# Supply_core.net
KiCad netlist of a schematic drawn in Altium Designer
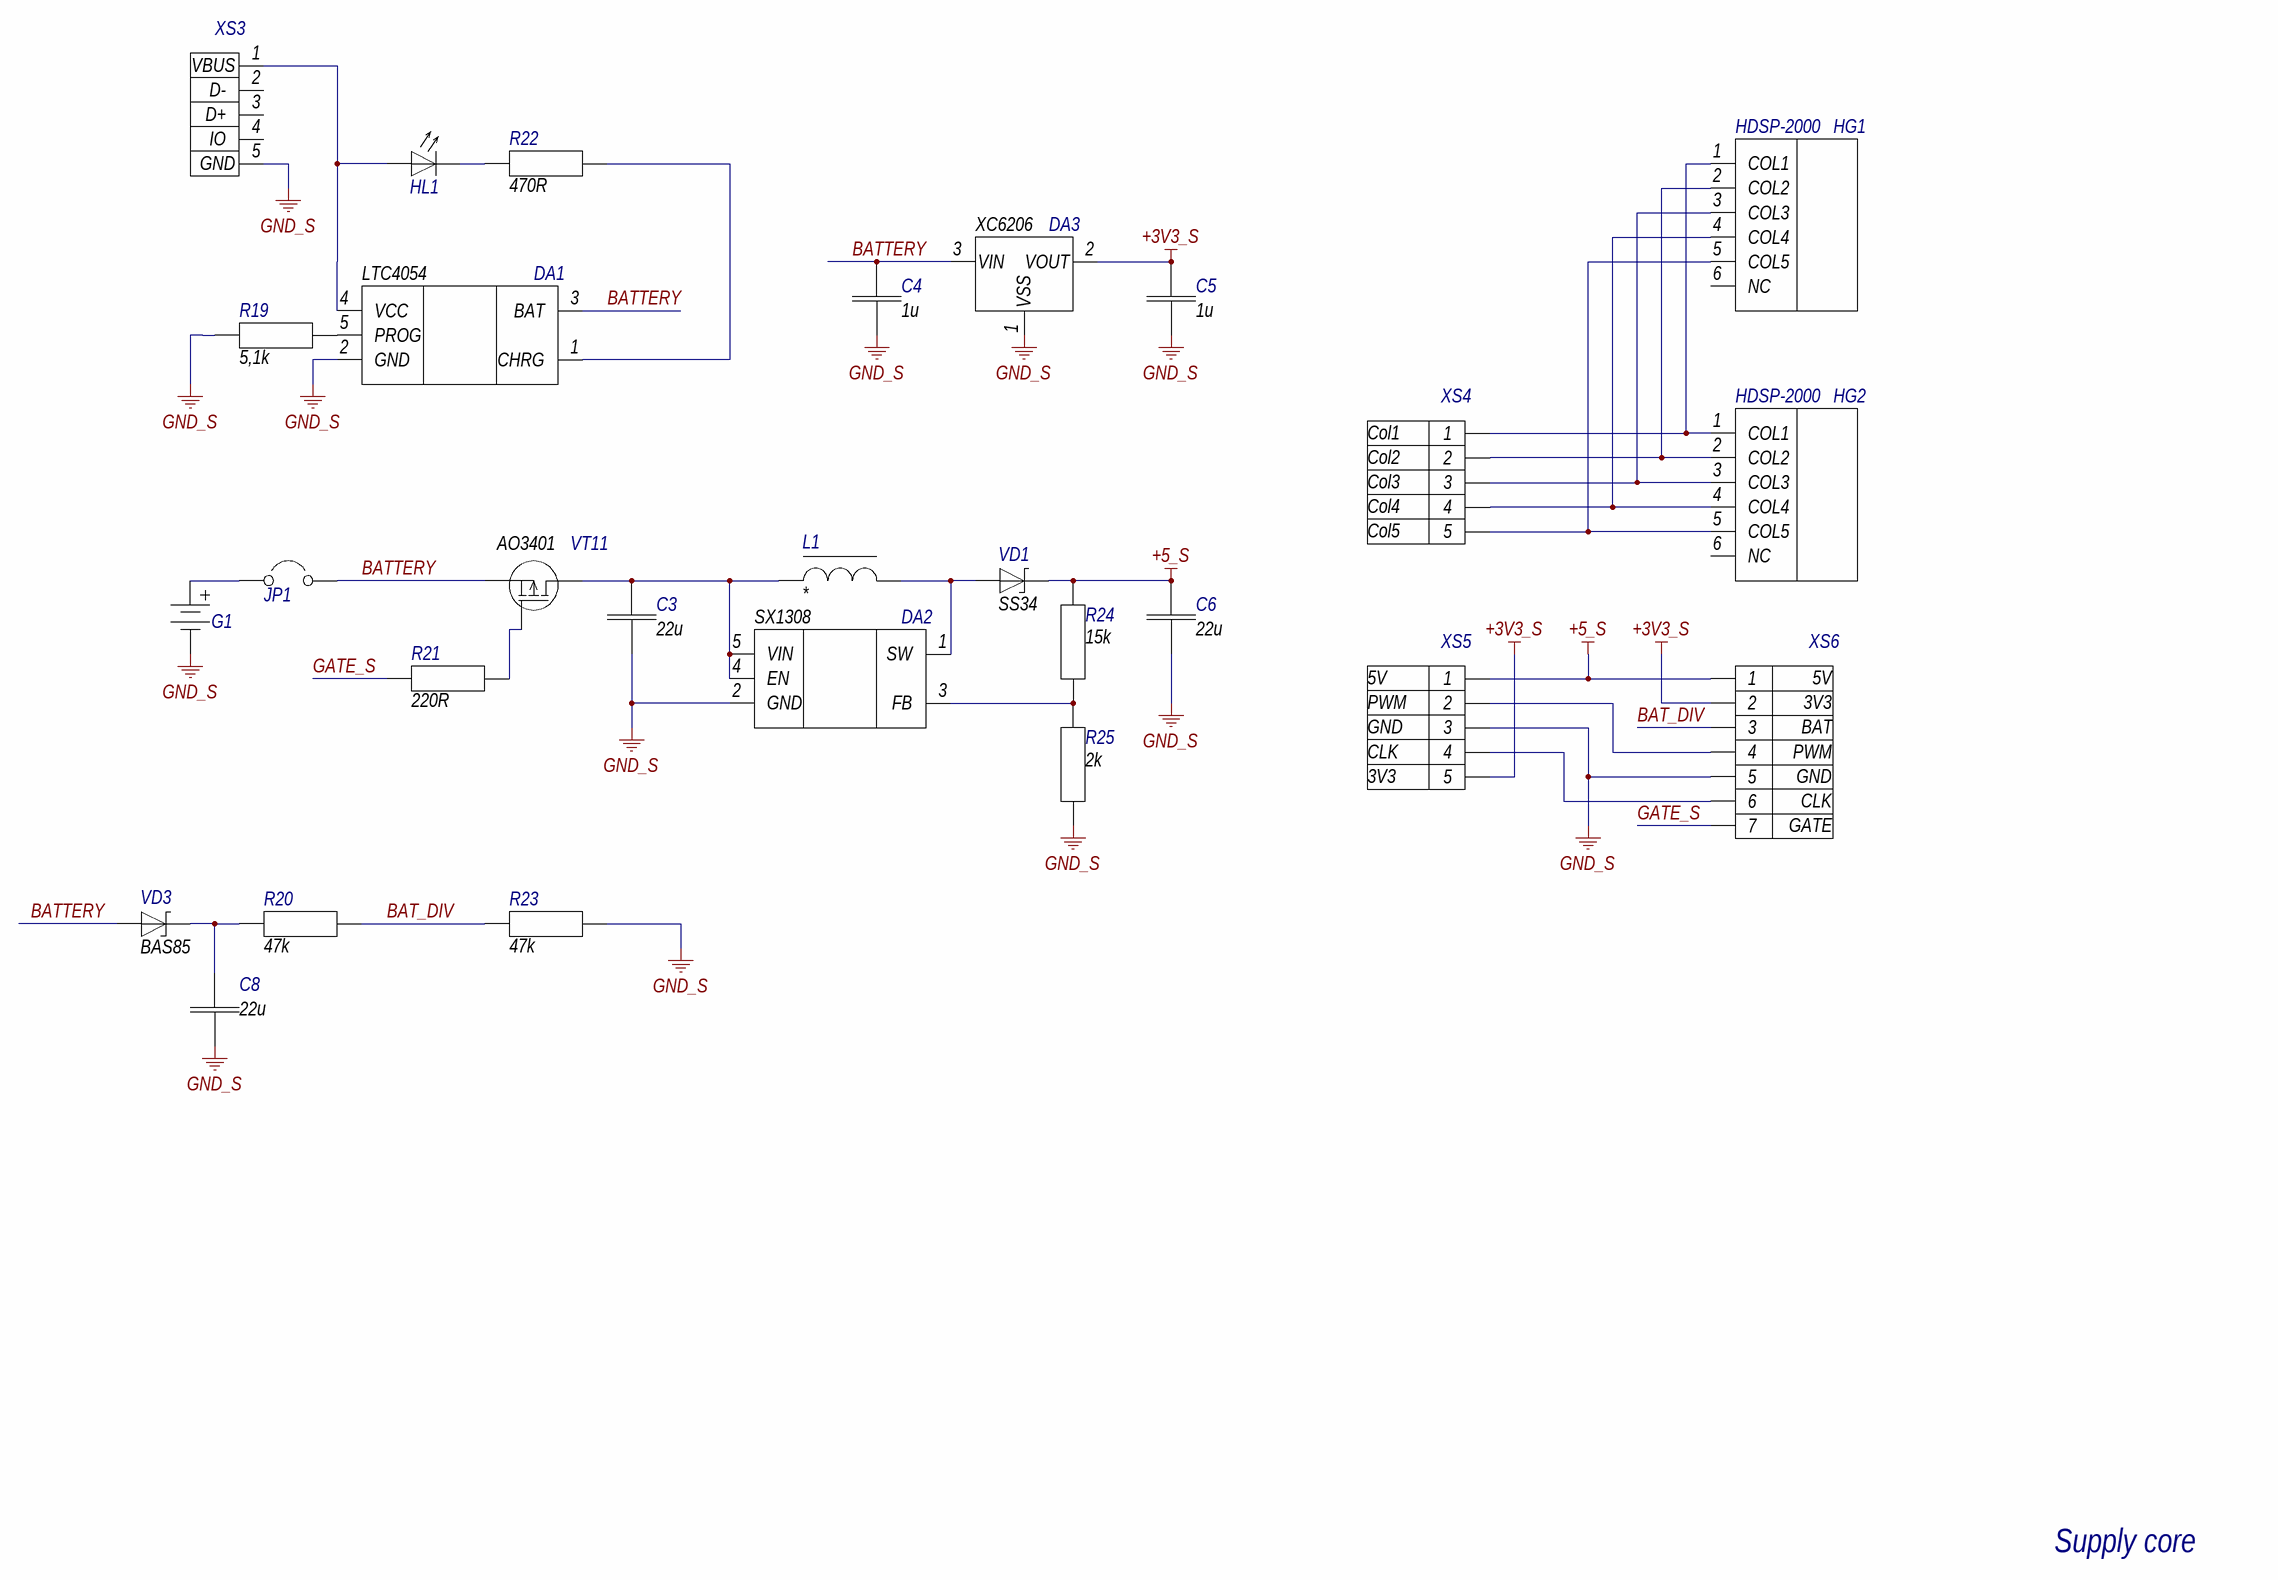
[diagram p0: Supply_core.SchDoc]

(export (version "E")
  (design (tool "Eeschema 10.0.6"))
  (components
    (comp (ref "C3")
      (value "22u")
      (footprint "CHIP-0805")
      (fields (field (name "Comment") "C0805"))
      (libsource (lib "Schlib1") (part "C0805"))
    )
    (comp (ref "C4")
      (value "1u")
      (footprint "CHIP-0603")
      (fields (field (name "Comment") "C0805"))
      (libsource (lib "Schlib1") (part "C0805"))
    )
    (comp (ref "C5")
      (value "1u")
      (footprint "CHIP-0603")
      (fields (field (name "Comment") "C0805"))
      (libsource (lib "Schlib1") (part "C0805"))
    )
    (comp (ref "C6")
      (value "22u")
      (footprint "CHIP-0805")
      (fields (field (name "Comment") "C0805"))
      (libsource (lib "Schlib1") (part "C0805"))
    )
    (comp (ref "C8")
      (value "22u")
      (footprint "CHIP-0805")
      (fields (field (name "Comment") "C0805"))
      (libsource (lib "Schlib1") (part "C0805"))
    )
    (comp (ref "DA1")
      (value "LTC4054")
      (footprint "SOT23-5")
      (fields (field (name "NAME") "LTC4054"))
      (libsource (lib "Schlib1") (part "LTC4054"))
    )
    (comp (ref "DA2")
      (value "SX1308")
      (footprint "SOT23-6")
      (fields (field (name "NAME") "SX1308"))
      (libsource (lib "Schlib1") (part "SX1308"))
    )
    (comp (ref "DA3")
      (value "XC6206")
      (footprint "SOT23-3")
      (fields (field (name "NAME") "XC6206"))
      (libsource (lib "Schlib1") (part "XC6206"))
    )
    (comp (ref "G1") (value "Battery") (footprint "BATTERY") (libsource (lib "Schlib1") (part "Battery")))
    (comp (ref "HG1")
      (value "HDSP-2000_Colums")
      (footprint "HDSP-2000_COL")
      (fields (field (name "MANUFACTURER") "HP") (field (name "NAME") "HDSP-2000"))
      (libsource (lib "Schlib1") (part "HDSP-2000_Colums"))
    )
    (comp (ref "HG2")
      (value "HDSP-2000_Colums")
      (footprint "HDSP-2000_COL")
      (fields (field (name "MANUFACTURER") "HP") (field (name "NAME") "HDSP-2000"))
      (libsource (lib "Schlib1") (part "HDSP-2000_Colums"))
    )
    (comp (ref "HL1") (value "LED") (footprint "LED_1") (libsource (lib "Schlib1") (part "LED")))
    (comp (ref "JP1") (value "Jamper") (footprint "JAMPER") (libsource (lib "Schlib1") (part "Jamper")))
    (comp (ref "L1")
      (value "L")
      (footprint "L_SMD")
      (fields (field (name "ALTIUM_VALUE") "*"))
      (libsource (lib "Schlib1") (part "L"))
    )
    (comp (ref "R19")
      (value "5,1k")
      (footprint "CHIP-0402")
      (fields (field (name "Comment") "R0805"))
      (libsource (lib "") (part "R0805_1"))
    )
    (comp (ref "R20")
      (value "47k")
      (footprint "CHIP-0402")
      (fields (field (name "Comment") "R0805"))
      (libsource (lib "") (part "R0805_1"))
    )
    (comp (ref "R21")
      (value "220R")
      (footprint "CHIP-0805")
      (fields (field (name "Comment") "R0805"))
      (libsource (lib "") (part "R0805_1"))
    )
    (comp (ref "R22")
      (value "470R")
      (footprint "CHIP-0805")
      (fields (field (name "Comment") "R0805"))
      (libsource (lib "") (part "R0805_1"))
    )
    (comp (ref "R23")
      (value "47k")
      (footprint "CHIP-0402")
      (fields (field (name "Comment") "R0805"))
      (libsource (lib "") (part "R0805_1"))
    )
    (comp (ref "R24")
      (value "15k")
      (footprint "CHIP-0805")
      (fields (field (name "Comment") "R0805"))
      (libsource (lib "Schlib1") (part "R0805"))
    )
    (comp (ref "R25")
      (value "2k")
      (footprint "CHIP-0805")
      (fields (field (name "Comment") "R0805"))
      (libsource (lib "Schlib1") (part "R0805"))
    )
    (comp (ref "VD1")
      (value "SS34")
      (footprint "DIOD")
      (fields (field (name "NAME") "SS34"))
      (libsource (lib "Schlib1") (part "SS34"))
    )
    (comp (ref "VD3")
      (value "BAS85")
      (footprint "DIOD_MELF")
      (fields (field (name "NAME") "BAS85"))
      (libsource (lib "Schlib1") (part "BAS85"))
    )
    (comp (ref "VT11")
      (value "AO3401A")
      (footprint "SOT23-3")
      (fields (field (name "NAME") "AO3401"))
      (libsource (lib "Schlib1") (part "AO3401A"))
    )
    (comp (ref "XS3")
      (value "Micro_USB")
      (footprint "Micro_USB")
      (libsource (lib "Schlib1") (part "Micro_USB"))
    )
    (comp (ref "XS4")
      (value "Socket")
      (footprint "SOCKET")
      (fields
        (field (name "PIN5") "Col5")
        (field (name "PIN4") "Col4")
        (field (name "PIN3") "Col3")
        (field (name "PIN2") "Col2")
        (field (name "PIN1") "Col1")
      )
      (libsource (lib "Schlib1") (part "Socket"))
    )
    (comp (ref "XS5")
      (value "Socket")
      (footprint "SOCKET")
      (fields
        (field (name "PIN5") "3V3")
        (field (name "PIN4") "CLK")
        (field (name "PIN3") "GND")
        (field (name "PIN2") "PWM")
        (field (name "PIN1") "5V")
      )
      (libsource (lib "Schlib1") (part "Socket"))
    )
    (comp (ref "XS6")
      (value "Socket_7")
      (footprint "SOCKET_7")
      (fields
        (field (name "PIN7") "GATE")
        (field (name "PIN6") "CLK")
        (field (name "PIN5") "GND")
        (field (name "PIN4") "PWM")
        (field (name "PIN3") "BAT")
        (field (name "PIN2") "3V3")
        (field (name "PIN1") "5V")
      )
      (libsource (lib "Schlib1") (part "Socket_7"))
    )
  )
  (nets
    (net (code "1") (name "+3V3_S") (class "Default")
      (node (ref "C5") (pin "2") (pinfunction "2_2") (pintype "passive"))
      (node (ref "DA3") (pin "2") (pinfunction "VOUT_2") (pintype "passive"))
      (node (ref "XS5") (pin "5") (pinfunction "5_5") (pintype "passive"))
      (node (ref "XS6") (pin "2") (pinfunction "2_2") (pintype "passive"))
    )
    (net (code "2") (name "+5_S") (class "Default")
      (node (ref "C6") (pin "2") (pinfunction "2_2") (pintype "passive"))
      (node (ref "R24") (pin "2") (pinfunction "2_2") (pintype "passive"))
      (node (ref "VD1") (pin "1") (pinfunction "K_1") (pintype "passive"))
      (node (ref "XS5") (pin "1") (pinfunction "1_1") (pintype "passive"))
      (node (ref "XS6") (pin "1") (pinfunction "1_1") (pintype "passive"))
    )
    (net (code "3") (name "/BATTERY") (class "Default")
      (node (ref "C4") (pin "2") (pinfunction "2_2") (pintype "passive"))
      (node (ref "DA1") (pin "3") (pinfunction "BAT_3") (pintype "passive"))
      (node (ref "DA3") (pin "3") (pinfunction "VIN_3") (pintype "passive"))
      (node (ref "JP1") (pin "2") (pinfunction "2_2") (pintype "passive"))
      (node (ref "VD3") (pin "2") (pinfunction "A_2") (pintype "passive"))
      (node (ref "VT11") (pin "2") (pinfunction "S_2") (pintype "passive"))
    )
    (net (code "4") (name "/BAT_DIV") (class "Default")
      (node (ref "R20") (pin "2") (pinfunction "2_2") (pintype "passive"))
      (node (ref "R23") (pin "1") (pinfunction "1_1") (pintype "passive"))
      (node (ref "XS6") (pin "3") (pinfunction "3_3") (pintype "passive"))
    )
    (net (code "5") (name "/GATE_S") (class "Default")
      (node (ref "R21") (pin "1") (pinfunction "1_1") (pintype "passive"))
      (node (ref "XS6") (pin "7") (pinfunction "7_7") (pintype "passive"))
    )
    (net (code "6") (name "GND_S") (class "Default")
      (node (ref "C3") (pin "1") (pinfunction "1_1") (pintype "passive"))
      (node (ref "C4") (pin "1") (pinfunction "1_1") (pintype "passive"))
      (node (ref "C5") (pin "1") (pinfunction "1_1") (pintype "passive"))
      (node (ref "C6") (pin "1") (pinfunction "1_1") (pintype "passive"))
      (node (ref "C8") (pin "1") (pinfunction "1_1") (pintype "passive"))
      (node (ref "DA1") (pin "2") (pinfunction "GND_2") (pintype "passive"))
      (node (ref "DA2") (pin "2") (pinfunction "GND_2") (pintype "passive"))
      (node (ref "DA3") (pin "1") (pinfunction "VSS_1") (pintype "passive"))
      (node (ref "G1") (pin "2") (pinfunction "2_2") (pintype "passive"))
      (node (ref "R19") (pin "1") (pinfunction "1_1") (pintype "passive"))
      (node (ref "R23") (pin "2") (pinfunction "2_2") (pintype "passive"))
      (node (ref "R25") (pin "1") (pinfunction "1_1") (pintype "passive"))
      (node (ref "XS3") (pin "5") (pinfunction "GND_5") (pintype "passive"))
      (node (ref "XS5") (pin "3") (pinfunction "3_3") (pintype "passive"))
      (node (ref "XS6") (pin "5") (pinfunction "5_5") (pintype "passive"))
    )
    (net (code "7") (name "Net-(DA1-CHRG)") (class "Default")
      (node (ref "DA1") (pin "1") (pinfunction "CHRG_1") (pintype "passive"))
      (node (ref "R22") (pin "2") (pinfunction "2_2") (pintype "passive"))
    )
    (net (code "8") (name "Net-(DA1-PROG)") (class "Default")
      (node (ref "DA1") (pin "5") (pinfunction "PROG_5") (pintype "passive"))
      (node (ref "R19") (pin "2") (pinfunction "2_2") (pintype "passive"))
    )
    (net (code "9") (name "Net-(DA1-VCC)") (class "Default")
      (node (ref "DA1") (pin "4") (pinfunction "VCC_4") (pintype "passive"))
      (node (ref "HL1") (pin "2") (pinfunction "A_2") (pintype "passive"))
      (node (ref "XS3") (pin "1") (pinfunction "VBUS_1") (pintype "passive"))
    )
    (net (code "10") (name "Net-(DA2-EN)") (class "Default")
      (node (ref "C3") (pin "2") (pinfunction "2_2") (pintype "passive"))
      (node (ref "DA2") (pin "4") (pinfunction "EN_4") (pintype "passive"))
      (node (ref "DA2") (pin "5") (pinfunction "VIN_5") (pintype "passive"))
      (node (ref "L1") (pin "1") (pinfunction "1_1") (pintype "passive"))
      (node (ref "VT11") (pin "3") (pinfunction "D_3") (pintype "passive"))
    )
    (net (code "11") (name "Net-(DA2-FB)") (class "Default")
      (node (ref "DA2") (pin "3") (pinfunction "FB_3") (pintype "passive"))
      (node (ref "R24") (pin "1") (pinfunction "1_1") (pintype "passive"))
      (node (ref "R25") (pin "2") (pinfunction "2_2") (pintype "passive"))
    )
    (net (code "12") (name "Net-(DA2-SW)") (class "Default")
      (node (ref "DA2") (pin "1") (pinfunction "SW_1") (pintype "passive"))
      (node (ref "L1") (pin "2") (pinfunction "2_2") (pintype "passive"))
      (node (ref "VD1") (pin "2") (pinfunction "A_2") (pintype "passive"))
    )
    (net (code "13") (name "Net-(G1-Pad1)") (class "Default")
      (node (ref "G1") (pin "1") (pinfunction "1_1") (pintype "passive"))
      (node (ref "JP1") (pin "1") (pinfunction "1_1") (pintype "passive"))
    )
    (net (code "14") (name "Net-(HG1-COL1)") (class "Default")
      (node (ref "HG1") (pin "1") (pinfunction "COL1_1") (pintype "passive"))
      (node (ref "HG2") (pin "1") (pinfunction "COL1_1") (pintype "passive"))
      (node (ref "XS4") (pin "1") (pinfunction "1_1") (pintype "passive"))
    )
    (net (code "15") (name "Net-(HG1-COL2)") (class "Default")
      (node (ref "HG1") (pin "2") (pinfunction "COL2_2") (pintype "passive"))
      (node (ref "HG2") (pin "2") (pinfunction "COL2_2") (pintype "passive"))
      (node (ref "XS4") (pin "2") (pinfunction "2_2") (pintype "passive"))
    )
    (net (code "16") (name "Net-(HG1-COL3)") (class "Default")
      (node (ref "HG1") (pin "3") (pinfunction "COL3_3") (pintype "passive"))
      (node (ref "HG2") (pin "3") (pinfunction "COL3_3") (pintype "passive"))
      (node (ref "XS4") (pin "3") (pinfunction "3_3") (pintype "passive"))
    )
    (net (code "17") (name "Net-(HG1-COL4)") (class "Default")
      (node (ref "HG1") (pin "4") (pinfunction "COL4_4") (pintype "passive"))
      (node (ref "HG2") (pin "4") (pinfunction "COL4_4") (pintype "passive"))
      (node (ref "XS4") (pin "4") (pinfunction "4_4") (pintype "passive"))
    )
    (net (code "18") (name "Net-(HG1-COL5)") (class "Default")
      (node (ref "HG1") (pin "5") (pinfunction "COL5_5") (pintype "passive"))
      (node (ref "HG2") (pin "5") (pinfunction "COL5_5") (pintype "passive"))
      (node (ref "XS4") (pin "5") (pinfunction "5_5") (pintype "passive"))
    )
    (net (code "19") (name "Net-(HL1-K)") (class "Default")
      (node (ref "HL1") (pin "1") (pinfunction "K_1") (pintype "passive"))
      (node (ref "R22") (pin "1") (pinfunction "1_1") (pintype "passive"))
    )
    (net (code "20") (name "Net-(VD3-K)") (class "Default")
      (node (ref "C8") (pin "2") (pinfunction "2_2") (pintype "passive"))
      (node (ref "R20") (pin "1") (pinfunction "1_1") (pintype "passive"))
      (node (ref "VD3") (pin "1") (pinfunction "K_1") (pintype "passive"))
    )
    (net (code "21") (name "Net-(VT11-G)") (class "Default")
      (node (ref "R21") (pin "2") (pinfunction "2_2") (pintype "passive"))
      (node (ref "VT11") (pin "1") (pinfunction "G_1") (pintype "passive"))
    )
    (net (code "22") (name "Net-(XS5-Pad2)") (class "Default")
      (node (ref "XS5") (pin "2") (pinfunction "2_2") (pintype "passive"))
      (node (ref "XS6") (pin "4") (pinfunction "4_4") (pintype "passive"))
    )
    (net (code "23") (name "Net-(XS5-Pad4)") (class "Default")
      (node (ref "XS5") (pin "4") (pinfunction "4_4") (pintype "passive"))
      (node (ref "XS6") (pin "6") (pinfunction "6_6") (pintype "passive"))
    )
    (net (code "24") (name "unconnected-(HG1-NC-Pad6)") (class "Default")
      (node (ref "HG1") (pin "6") (pinfunction "NC_6") (pintype "passive"))
    )
    (net (code "25") (name "unconnected-(HG2-NC-Pad6)") (class "Default")
      (node (ref "HG2") (pin "6") (pinfunction "NC_6") (pintype "passive"))
    )
    (net (code "26") (name "unconnected-(XS3-D+-Pad3)") (class "Default")
      (node (ref "XS3") (pin "3") (pinfunction "D+_3") (pintype "passive"))
    )
    (net (code "27") (name "unconnected-(XS3-D--Pad2)") (class "Default")
      (node (ref "XS3") (pin "2") (pinfunction "D-_2") (pintype "passive"))
    )
    (net (code "28") (name "unconnected-(XS3-IO-Pad4)") (class "Default")
      (node (ref "XS3") (pin "4") (pinfunction "IO_4") (pintype "passive"))
    )
  )
)
